# GSM_LED_Indicators.net
KiCad netlist of a schematic drawn in Altium Designer
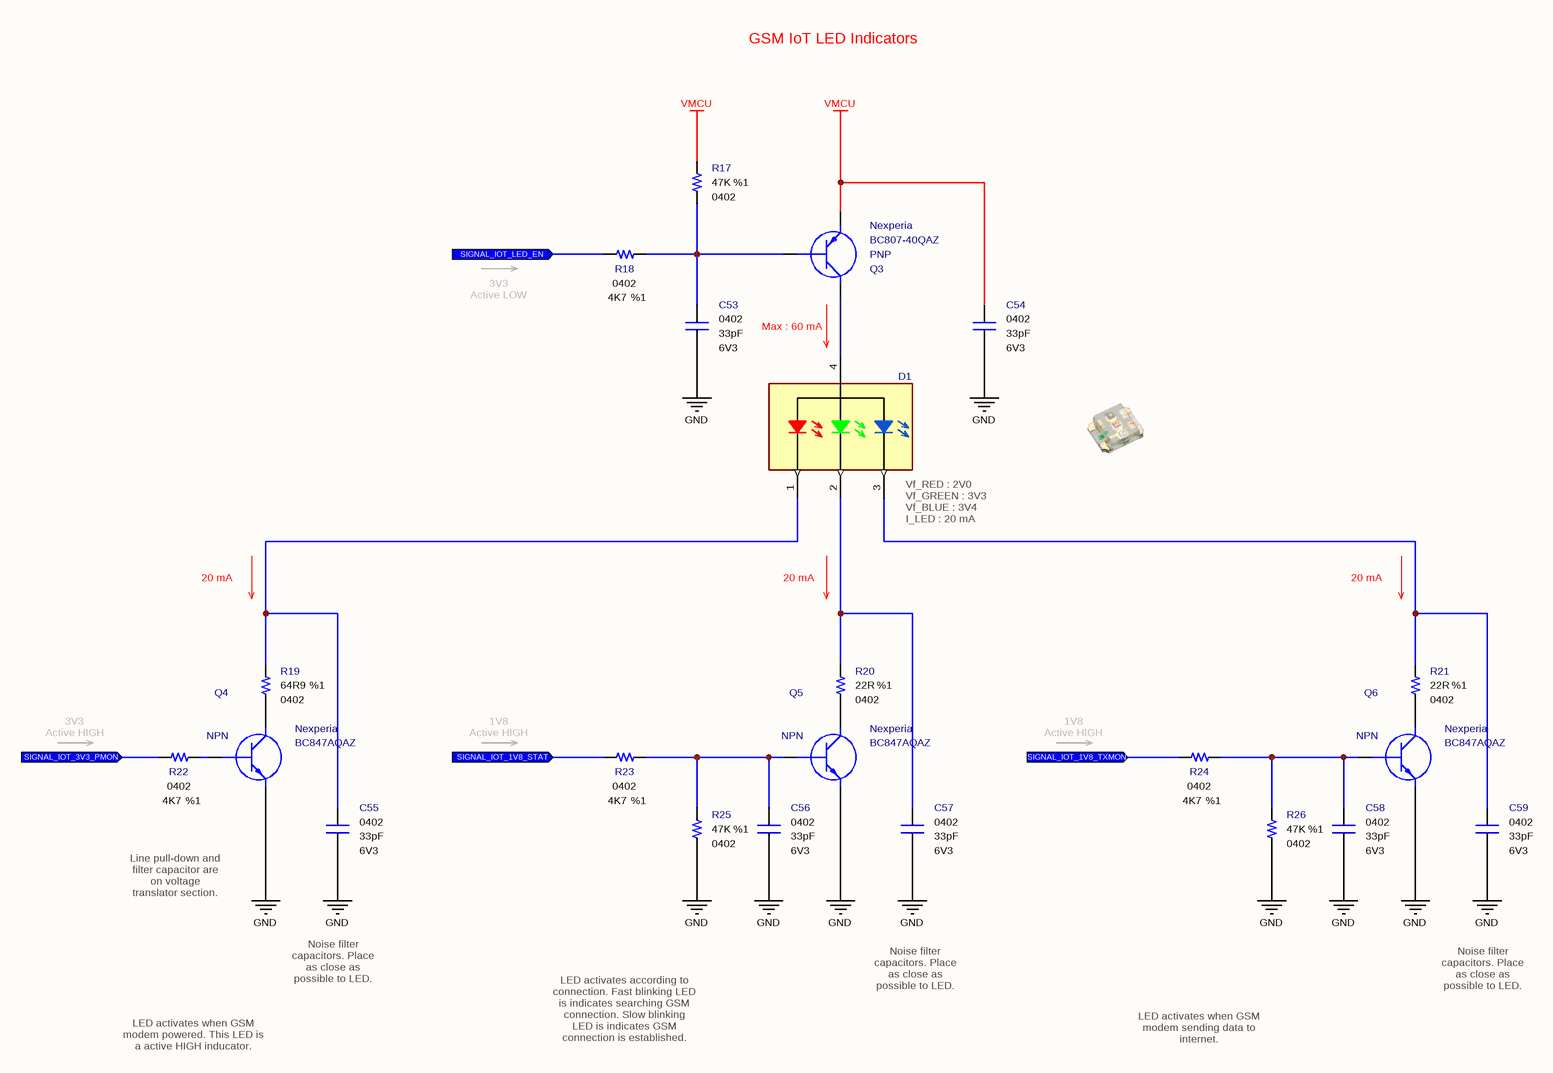
[diagram p0: GSM LED Indicators.SchDoc]

(export (version "E")
  (design (tool "Eeschema 10.0.6"))
  (components
    (comp (ref "C53")
      (value "33pF")
      (footprint "CAPACITOR_0402")
      (description "Capacitor - 33pF [0402] (Ceramic)")
      (fields
        (field (name "CASE") "0402")
        (field (name "TOLERANCE") "10%")
        (field (name "VOLTAGE") "6V3")
        (field (name "MANUFACTURER PART NUMBER") "C0402C330J9RACAUTO")
      )
      (libsource (lib "Ovoo_Library") (part "Capacitor - 33pF [0402-6V3]"))
    )
    (comp (ref "C54")
      (value "33pF")
      (footprint "CAPACITOR_0402")
      (description "Capacitor - 33pF [0402] (Ceramic)")
      (fields
        (field (name "CASE") "0402")
        (field (name "TOLERANCE") "10%")
        (field (name "VOLTAGE") "6V3")
        (field (name "MANUFACTURER PART NUMBER") "C0402C330J9RACAUTO")
      )
      (libsource (lib "Ovoo_Library") (part "Capacitor - 33pF [0402-6V3]"))
    )
    (comp (ref "C55")
      (value "33pF")
      (footprint "CAPACITOR_0402")
      (description "Capacitor - 33pF [0402] (Ceramic)")
      (fields
        (field (name "CASE") "0402")
        (field (name "TOLERANCE") "10%")
        (field (name "VOLTAGE") "6V3")
        (field (name "MANUFACTURER PART NUMBER") "C0402C330J9RACAUTO")
      )
      (libsource (lib "Ovoo_Library") (part "Capacitor - 33pF [0402-6V3]"))
    )
    (comp (ref "C56")
      (value "33pF")
      (footprint "CAPACITOR_0402")
      (description "Capacitor - 33pF [0402] (Ceramic)")
      (fields
        (field (name "CASE") "0402")
        (field (name "TOLERANCE") "10%")
        (field (name "VOLTAGE") "6V3")
        (field (name "MANUFACTURER PART NUMBER") "C0402C330J9RACAUTO")
      )
      (libsource (lib "Ovoo_Library") (part "Capacitor - 33pF [0402-6V3]"))
    )
    (comp (ref "C57")
      (value "33pF")
      (footprint "CAPACITOR_0402")
      (description "Capacitor - 33pF [0402] (Ceramic)")
      (fields
        (field (name "CASE") "0402")
        (field (name "TOLERANCE") "10%")
        (field (name "VOLTAGE") "6V3")
        (field (name "MANUFACTURER PART NUMBER") "C0402C330J9RACAUTO")
      )
      (libsource (lib "Ovoo_Library") (part "Capacitor - 33pF [0402-6V3]"))
    )
    (comp (ref "C58")
      (value "33pF")
      (footprint "CAPACITOR_0402")
      (description "Capacitor - 33pF [0402] (Ceramic)")
      (fields
        (field (name "CASE") "0402")
        (field (name "TOLERANCE") "10%")
        (field (name "VOLTAGE") "6V3")
        (field (name "MANUFACTURER PART NUMBER") "C0402C330J9RACAUTO")
      )
      (libsource (lib "Ovoo_Library") (part "Capacitor - 33pF [0402-6V3]"))
    )
    (comp (ref "C59")
      (value "33pF")
      (footprint "CAPACITOR_0402")
      (description "Capacitor - 33pF [0402] (Ceramic)")
      (fields
        (field (name "CASE") "0402")
        (field (name "TOLERANCE") "10%")
        (field (name "VOLTAGE") "6V3")
        (field (name "MANUFACTURER PART NUMBER") "C0402C330J9RACAUTO")
      )
      (libsource (lib "Ovoo_Library") (part "Capacitor - 33pF [0402-6V3]"))
    )
    (comp (ref "D1")
      (value "150066M153000")
      (footprint "Wurth_0606")
      (description "Standard LEDs - SMD PICOLED series Red LED")
      (fields (field (name "MOUSER PART NUMBER") "710-150066M153000"))
      (libsource (lib "Ovoo_Library") (part "Diode - RGB LED (150066M153000)"))
    )
    (comp (ref "Q3")
      (value "Bipolar PNP Transistors")
      (footprint "SOT1215")
      (description "Bipolar Transistors - BJT 45 V, 500 mA PNP gen purpose transistors")
      (fields
        (field (name "MOUSER PART NUMBER") "771-BC807-40QAZ")
        (field (name "POLARITY") "PNP")
        (field (name "MANUFACTURER NAME") "Nexperia")
        (field (name "MANUFACTURER PART NUMBER") "BC807-40QAZ")
      )
      (libsource (lib "Ovoo_Library") (part "Transistor - BC807"))
    )
    (comp (ref "Q4")
      (value "Bipolar NPN Transistors")
      (footprint "SOT1215")
      (description "Bipolar Transistors - BJT BC847AQA/DFN1010D-3/REEL 7\" Q2")
      (fields
        (field (name "POLARITY") "NPN")
        (field (name "MOUSER PART NUMBER") "771-BC847AQAZ")
        (field (name "MANUFACTURER NAME") "Nexperia")
        (field (name "MANUFACTURER PART NUMBER") "BC847AQAZ")
      )
      (libsource (lib "Ovoo_Library") (part "Transistor - BC847"))
    )
    (comp (ref "Q5")
      (value "Bipolar NPN Transistors")
      (footprint "SOT1215")
      (description "Bipolar Transistors - BJT BC847AQA/DFN1010D-3/REEL 7\" Q2")
      (fields
        (field (name "POLARITY") "NPN")
        (field (name "MOUSER PART NUMBER") "771-BC847AQAZ")
        (field (name "MANUFACTURER NAME") "Nexperia")
        (field (name "MANUFACTURER PART NUMBER") "BC847AQAZ")
      )
      (libsource (lib "Ovoo_Library") (part "Transistor - BC847"))
    )
    (comp (ref "Q6")
      (value "Bipolar NPN Transistors")
      (footprint "SOT1215")
      (description "Bipolar Transistors - BJT BC847AQA/DFN1010D-3/REEL 7\" Q2")
      (fields
        (field (name "POLARITY") "NPN")
        (field (name "MOUSER PART NUMBER") "771-BC847AQAZ")
        (field (name "MANUFACTURER NAME") "Nexperia")
        (field (name "MANUFACTURER PART NUMBER") "BC847AQAZ")
      )
      (libsource (lib "Ovoo_Library") (part "Transistor - BC847"))
    )
    (comp (ref "R17")
      (value "47K")
      (footprint "RESISTOR_0402")
      (description "Thick Film Resistors - SMD 1/16 W 47 Kohms 1%")
      (fields
        (field (name "TOLERANCE") "%1")
        (field (name "CASE") "0402")
        (field (name "MANUFACTURER PART NUMBER") "CRCW040247K0FKED")
        (field (name "MOUSER PART NUMBER") "71-CRCW0402-47K-E3")
      )
      (libsource (lib "Ovoo_Library") (part "Resistor - 47K"))
    )
    (comp (ref "R18")
      (value "4K7")
      (footprint "RESISTOR_0402")
      (description "Thick Film Resistors - SMD 1/16 W 4.7 Kohms 1%")
      (fields
        (field (name "MANUFACTURER PART NUMBER") "CRCW04024K70FKED")
        (field (name "MOUSER PART NUMBER") "71-CRCW0402-4.7K-E3")
        (field (name "TOLERANCE") "%1")
        (field (name "CASE") "0402")
      )
      (libsource (lib "Ovoo_Library") (part "Resistor - 4K7"))
    )
    (comp (ref "R19")
      (value "64R9")
      (footprint "RESISTOR_0402")
      (description "Thick Film Resistors - SMD 1/16 W 64R9 Ohms 1%")
      (fields
        (field (name "MANUFACTURER PART NUMBER") "CRCW040264R9FKED")
        (field (name "MOUSER PART NUMBER") "71-CRCW0402-64.9-E3")
        (field (name "TOLERANCE") "%1")
        (field (name "CASE") "0402")
      )
      (libsource (lib "Ovoo_Library") (part "Resistor - 64R9"))
    )
    (comp (ref "R20")
      (value "22R")
      (footprint "RESISTOR_0402")
      (description "Thick Film Resistors - SMD 1/16 W 22R Ohms 1%")
      (fields
        (field (name "MANUFACTURER PART NUMBER") "CRCW040222R0FKED")
        (field (name "MOUSER PART NUMBER") "71-CRCW0402-22-E3")
        (field (name "TOLERANCE") "%1")
        (field (name "CASE") "0402")
      )
      (libsource (lib "Ovoo_Library") (part "Resistor - 22R"))
    )
    (comp (ref "R21")
      (value "22R")
      (footprint "RESISTOR_0402")
      (description "Thick Film Resistors - SMD 1/16 W 22R Ohms 1%")
      (fields
        (field (name "MANUFACTURER PART NUMBER") "CRCW040222R0FKED")
        (field (name "MOUSER PART NUMBER") "71-CRCW0402-22-E3")
        (field (name "TOLERANCE") "%1")
        (field (name "CASE") "0402")
      )
      (libsource (lib "Ovoo_Library") (part "Resistor - 22R"))
    )
    (comp (ref "R22")
      (value "4K7")
      (footprint "RESISTOR_0402")
      (description "Thick Film Resistors - SMD 1/16 W 4.7 Kohms 1%")
      (fields
        (field (name "MANUFACTURER PART NUMBER") "CRCW04024K70FKED")
        (field (name "MOUSER PART NUMBER") "71-CRCW0402-4.7K-E3")
        (field (name "TOLERANCE") "%1")
        (field (name "CASE") "0402")
      )
      (libsource (lib "Ovoo_Library") (part "Resistor - 4K7"))
    )
    (comp (ref "R23")
      (value "4K7")
      (footprint "RESISTOR_0402")
      (description "Thick Film Resistors - SMD 1/16 W 4.7 Kohms 1%")
      (fields
        (field (name "MANUFACTURER PART NUMBER") "CRCW04024K70FKED")
        (field (name "MOUSER PART NUMBER") "71-CRCW0402-4.7K-E3")
        (field (name "TOLERANCE") "%1")
        (field (name "CASE") "0402")
      )
      (libsource (lib "Ovoo_Library") (part "Resistor - 4K7"))
    )
    (comp (ref "R24")
      (value "4K7")
      (footprint "RESISTOR_0402")
      (description "Thick Film Resistors - SMD 1/16 W 4.7 Kohms 1%")
      (fields
        (field (name "MANUFACTURER PART NUMBER") "CRCW04024K70FKED")
        (field (name "MOUSER PART NUMBER") "71-CRCW0402-4.7K-E3")
        (field (name "TOLERANCE") "%1")
        (field (name "CASE") "0402")
      )
      (libsource (lib "Ovoo_Library") (part "Resistor - 4K7"))
    )
    (comp (ref "R25")
      (value "47K")
      (footprint "RESISTOR_0402")
      (description "Thick Film Resistors - SMD 1/16 W 47 Kohms 1%")
      (fields
        (field (name "TOLERANCE") "%1")
        (field (name "CASE") "0402")
        (field (name "MANUFACTURER PART NUMBER") "CRCW040247K0FKED")
        (field (name "MOUSER PART NUMBER") "71-CRCW0402-47K-E3")
      )
      (libsource (lib "Ovoo_Library") (part "Resistor - 47K"))
    )
    (comp (ref "R26")
      (value "47K")
      (footprint "RESISTOR_0402")
      (description "Thick Film Resistors - SMD 1/16 W 47 Kohms 1%")
      (fields
        (field (name "TOLERANCE") "%1")
        (field (name "CASE") "0402")
        (field (name "MANUFACTURER PART NUMBER") "CRCW040247K0FKED")
        (field (name "MOUSER PART NUMBER") "71-CRCW0402-47K-E3")
      )
      (libsource (lib "Ovoo_Library") (part "Resistor - 47K"))
    )
  )
  (nets
    (net (code "1") (name "/SIGNAL_IOT_1V8_STAT") (class "Default")
      (node (ref "R23") (pin "2") (pinfunction "2_2") (pintype "passive"))
    )
    (net (code "2") (name "/SIGNAL_IOT_1V8_TXMON") (class "Default")
      (node (ref "R24") (pin "2") (pinfunction "2_2") (pintype "passive"))
    )
    (net (code "3") (name "/SIGNAL_IOT_3V3_PMON") (class "Default")
      (node (ref "R22") (pin "2") (pinfunction "2_2") (pintype "passive"))
    )
    (net (code "4") (name "/SIGNAL_IOT_LED_EN") (class "Default")
      (node (ref "R18") (pin "2") (pinfunction "2_2") (pintype "passive"))
    )
    (net (code "5") (name "GND") (class "Default")
      (node (ref "C53") (pin "2") (pinfunction "2_2") (pintype "passive"))
      (node (ref "C54") (pin "2") (pinfunction "2_2") (pintype "passive"))
      (node (ref "C55") (pin "2") (pinfunction "2_2") (pintype "passive"))
      (node (ref "C56") (pin "2") (pinfunction "2_2") (pintype "passive"))
      (node (ref "C57") (pin "2") (pinfunction "2_2") (pintype "passive"))
      (node (ref "C58") (pin "2") (pinfunction "2_2") (pintype "passive"))
      (node (ref "C59") (pin "2") (pinfunction "2_2") (pintype "passive"))
      (node (ref "Q4") (pin "2") (pinfunction "E_2") (pintype "passive"))
      (node (ref "Q5") (pin "2") (pinfunction "E_2") (pintype "passive"))
      (node (ref "Q6") (pin "2") (pinfunction "E_2") (pintype "passive"))
      (node (ref "R25") (pin "1") (pinfunction "1_1") (pintype "passive"))
      (node (ref "R26") (pin "1") (pinfunction "1_1") (pintype "passive"))
    )
    (net (code "6") (name "Net-(C55-Pad1)") (class "Default")
      (node (ref "C55") (pin "1") (pinfunction "1_1") (pintype "passive"))
      (node (ref "D1") (pin "1") (pinfunction "1_1") (pintype "output"))
      (node (ref "R19") (pin "2") (pinfunction "2_2") (pintype "passive"))
    )
    (net (code "7") (name "Net-(C57-Pad1)") (class "Default")
      (node (ref "C57") (pin "1") (pinfunction "1_1") (pintype "passive"))
      (node (ref "D1") (pin "2") (pinfunction "2_2") (pintype "output"))
      (node (ref "R20") (pin "2") (pinfunction "2_2") (pintype "passive"))
    )
    (net (code "8") (name "Net-(C59-Pad1)") (class "Default")
      (node (ref "C59") (pin "1") (pinfunction "1_1") (pintype "passive"))
      (node (ref "D1") (pin "3") (pinfunction "3_3") (pintype "output"))
      (node (ref "R21") (pin "2") (pinfunction "2_2") (pintype "passive"))
    )
    (net (code "9") (name "Net-(Q3-B)") (class "Default")
      (node (ref "C53") (pin "1") (pinfunction "1_1") (pintype "passive"))
      (node (ref "Q3") (pin "1") (pinfunction "B_1") (pintype "passive"))
      (node (ref "R17") (pin "1") (pinfunction "1_1") (pintype "passive"))
      (node (ref "R18") (pin "1") (pinfunction "1_1") (pintype "passive"))
    )
    (net (code "10") (name "Net-(Q3-C)") (class "Default")
      (node (ref "D1") (pin "4") (pinfunction "4_4") (pintype "power_in"))
      (node (ref "Q3") (pin "3") (pinfunction "C_3") (pintype "passive"))
    )
    (net (code "11") (name "Net-(Q4-B)") (class "Default")
      (node (ref "Q4") (pin "1") (pinfunction "B_1") (pintype "passive"))
      (node (ref "R22") (pin "1") (pinfunction "1_1") (pintype "passive"))
    )
    (net (code "12") (name "Net-(Q4-C)") (class "Default")
      (node (ref "Q4") (pin "3") (pinfunction "C_3") (pintype "passive"))
      (node (ref "R19") (pin "1") (pinfunction "1_1") (pintype "passive"))
    )
    (net (code "13") (name "Net-(Q5-B)") (class "Default")
      (node (ref "C56") (pin "1") (pinfunction "1_1") (pintype "passive"))
      (node (ref "Q5") (pin "1") (pinfunction "B_1") (pintype "passive"))
      (node (ref "R23") (pin "1") (pinfunction "1_1") (pintype "passive"))
      (node (ref "R25") (pin "2") (pinfunction "2_2") (pintype "passive"))
    )
    (net (code "14") (name "Net-(Q5-C)") (class "Default")
      (node (ref "Q5") (pin "3") (pinfunction "C_3") (pintype "passive"))
      (node (ref "R20") (pin "1") (pinfunction "1_1") (pintype "passive"))
    )
    (net (code "15") (name "Net-(Q6-B)") (class "Default")
      (node (ref "C58") (pin "1") (pinfunction "1_1") (pintype "passive"))
      (node (ref "Q6") (pin "1") (pinfunction "B_1") (pintype "passive"))
      (node (ref "R24") (pin "1") (pinfunction "1_1") (pintype "passive"))
      (node (ref "R26") (pin "2") (pinfunction "2_2") (pintype "passive"))
    )
    (net (code "16") (name "Net-(Q6-C)") (class "Default")
      (node (ref "Q6") (pin "3") (pinfunction "C_3") (pintype "passive"))
      (node (ref "R21") (pin "1") (pinfunction "1_1") (pintype "passive"))
    )
    (net (code "17") (name "VMCU") (class "Default")
      (node (ref "C54") (pin "1") (pinfunction "1_1") (pintype "passive"))
      (node (ref "Q3") (pin "2") (pinfunction "E_2") (pintype "passive"))
      (node (ref "R17") (pin "2") (pinfunction "2_2") (pintype "passive"))
    )
  )
)
